# rtc.net
KiCad netlist of a schematic drawn in EAGLE
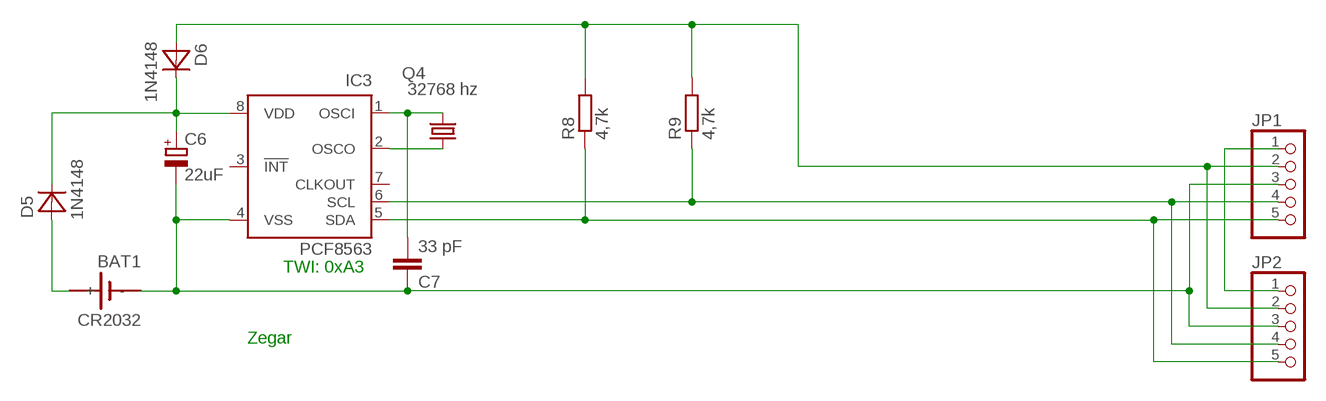
[diagram p0: schematic, sheet 1]

(export (version "E")
  (design (tool "Eeschema 10.0.6"))
  (components
    (comp (ref "BAT1")
      (value "CR2032")
      (footprint "eagle-import:SN2932_LISPOL")
      (libsource (lib "eagle-import") (part "SN2032LISPOL"))
    )
    (comp (ref "C6")
      (value "22uF")
      (footprint "eagle-import:E2,5-5")
      (libsource (lib "eagle-import") (part "CPOL-EUE2.5-5"))
    )
    (comp (ref "C7")
      (value "33 pF")
      (footprint "eagle-import:C050-024X044")
      (libsource (lib "eagle-import") (part "C-EU050-024X044"))
    )
    (comp (ref "D5")
      (value "1N4148")
      (footprint "eagle-import:DO35-7")
      (libsource (lib "eagle-import") (part "1N4148"))
    )
    (comp (ref "D6")
      (value "1N4148")
      (footprint "eagle-import:DO35-7")
      (libsource (lib "eagle-import") (part "1N4148"))
    )
    (comp (ref "IC3")
      (value "PCF8563")
      (footprint "eagle-import:DIL08")
      (libsource (lib "eagle-import") (part "PCF8563"))
    )
    (comp (ref "JP1")
      (value "PINHD-1X5/90")
      (footprint "eagle-import:1X05_90")
      (libsource (lib "eagle-import") (part "PINHD-1X5/90"))
    )
    (comp (ref "JP2")
      (value "PINHD-1X5/90")
      (footprint "eagle-import:1X05_90")
      (libsource (lib "eagle-import") (part "PINHD-1X5/90"))
    )
    (comp (ref "Q4")
      (value "32768 hz")
      (footprint "eagle-import:TC26V")
      (libsource (lib "eagle-import") (part "CRYSTALTC26V"))
    )
    (comp (ref "R8")
      (value "4,7k")
      (footprint "eagle-import:R1206")
      (libsource (lib "eagle-import") (part "R-EU_R1206"))
    )
    (comp (ref "R9")
      (value "4,7k")
      (footprint "eagle-import:R1206")
      (libsource (lib "eagle-import") (part "R-EU_R1206"))
    )
  )
  (nets
    (net (code "1") (name "Net-(BAT1-Pad+)") (class "Default")
      (node (ref "BAT1") (pin "+") (pinfunction "+_+") (pintype "passive"))
      (node (ref "D5") (pin "A") (pinfunction "A_A") (pintype "passive"))
    )
    (net (code "2") (name "Net-(D6-PadA)") (class "Default")
      (node (ref "D6") (pin "A") (pinfunction "A_A") (pintype "passive"))
      (node (ref "JP1") (pin "2") (pinfunction "2_2") (pintype "passive"))
      (node (ref "JP2") (pin "2") (pinfunction "2_2") (pintype "passive"))
      (node (ref "R8") (pin "2") (pinfunction "2_2") (pintype "passive"))
      (node (ref "R9") (pin "2") (pinfunction "2_2") (pintype "passive"))
    )
    (net (code "3") (name "Net-(IC3-OSCI)") (class "Default")
      (node (ref "C7") (pin "2") (pinfunction "2_2") (pintype "passive"))
      (node (ref "IC3") (pin "1") (pinfunction "OSCI_1") (pintype "input"))
      (node (ref "Q4") (pin "2") (pinfunction "2_2") (pintype "passive"))
    )
    (net (code "4") (name "Net-(IC3-OSCO)") (class "Default")
      (node (ref "IC3") (pin "2") (pinfunction "OSCO_2") (pintype "output"))
      (node (ref "Q4") (pin "1") (pinfunction "1_1") (pintype "passive"))
    )
    (net (code "5") (name "Net-(IC3-SCL)") (class "Default")
      (node (ref "IC3") (pin "6") (pinfunction "SCL_6") (pintype "input"))
      (node (ref "JP1") (pin "4") (pinfunction "4_4") (pintype "passive"))
      (node (ref "JP2") (pin "4") (pinfunction "4_4") (pintype "passive"))
      (node (ref "R9") (pin "1") (pinfunction "1_1") (pintype "passive"))
    )
    (net (code "6") (name "Net-(IC3-SDA)") (class "Default")
      (node (ref "IC3") (pin "5") (pinfunction "SDA_5") (pintype "bidirectional"))
      (node (ref "JP1") (pin "5") (pinfunction "5_5") (pintype "passive"))
      (node (ref "JP2") (pin "5") (pinfunction "5_5") (pintype "passive"))
      (node (ref "R8") (pin "1") (pinfunction "1_1") (pintype "passive"))
    )
    (net (code "7") (name "Net-(IC3-VDD)") (class "Default")
      (node (ref "C6") (pin "+") (pinfunction "+_+") (pintype "passive"))
      (node (ref "D5") (pin "C") (pinfunction "C_C") (pintype "passive"))
      (node (ref "D6") (pin "C") (pinfunction "C_C") (pintype "passive"))
      (node (ref "IC3") (pin "8") (pinfunction "VDD_8") (pintype "power_in"))
    )
    (net (code "8") (name "Net-(IC3-VSS)") (class "Default")
      (node (ref "BAT1") (pin "-") (pinfunction "-_-") (pintype "passive"))
      (node (ref "C6") (pin "-") (pinfunction "-_-") (pintype "passive"))
      (node (ref "C7") (pin "1") (pinfunction "1_1") (pintype "passive"))
      (node (ref "IC3") (pin "4") (pinfunction "VSS_4") (pintype "power_in"))
      (node (ref "JP1") (pin "3") (pinfunction "3_3") (pintype "passive"))
      (node (ref "JP2") (pin "3") (pinfunction "3_3") (pintype "passive"))
    )
    (net (code "9") (name "Net-(JP1-Pad1)") (class "Default")
      (node (ref "JP1") (pin "1") (pinfunction "1_1") (pintype "passive"))
      (node (ref "JP2") (pin "1") (pinfunction "1_1") (pintype "passive"))
    )
    (net (code "10") (name "unconnected-(IC3-CLKOUT-Pad7)") (class "Default")
      (node (ref "IC3") (pin "7") (pinfunction "CLKOUT_7") (pintype "output"))
    )
    (net (code "11") (name "unconnected-(IC3-~{INT}-Pad3)") (class "Default")
      (node (ref "IC3") (pin "3") (pinfunction "~{INT}_3") (pintype "output"))
    )
  )
)
